# div_Ele.net
KiCad netlist of a schematic drawn in Altium Designer
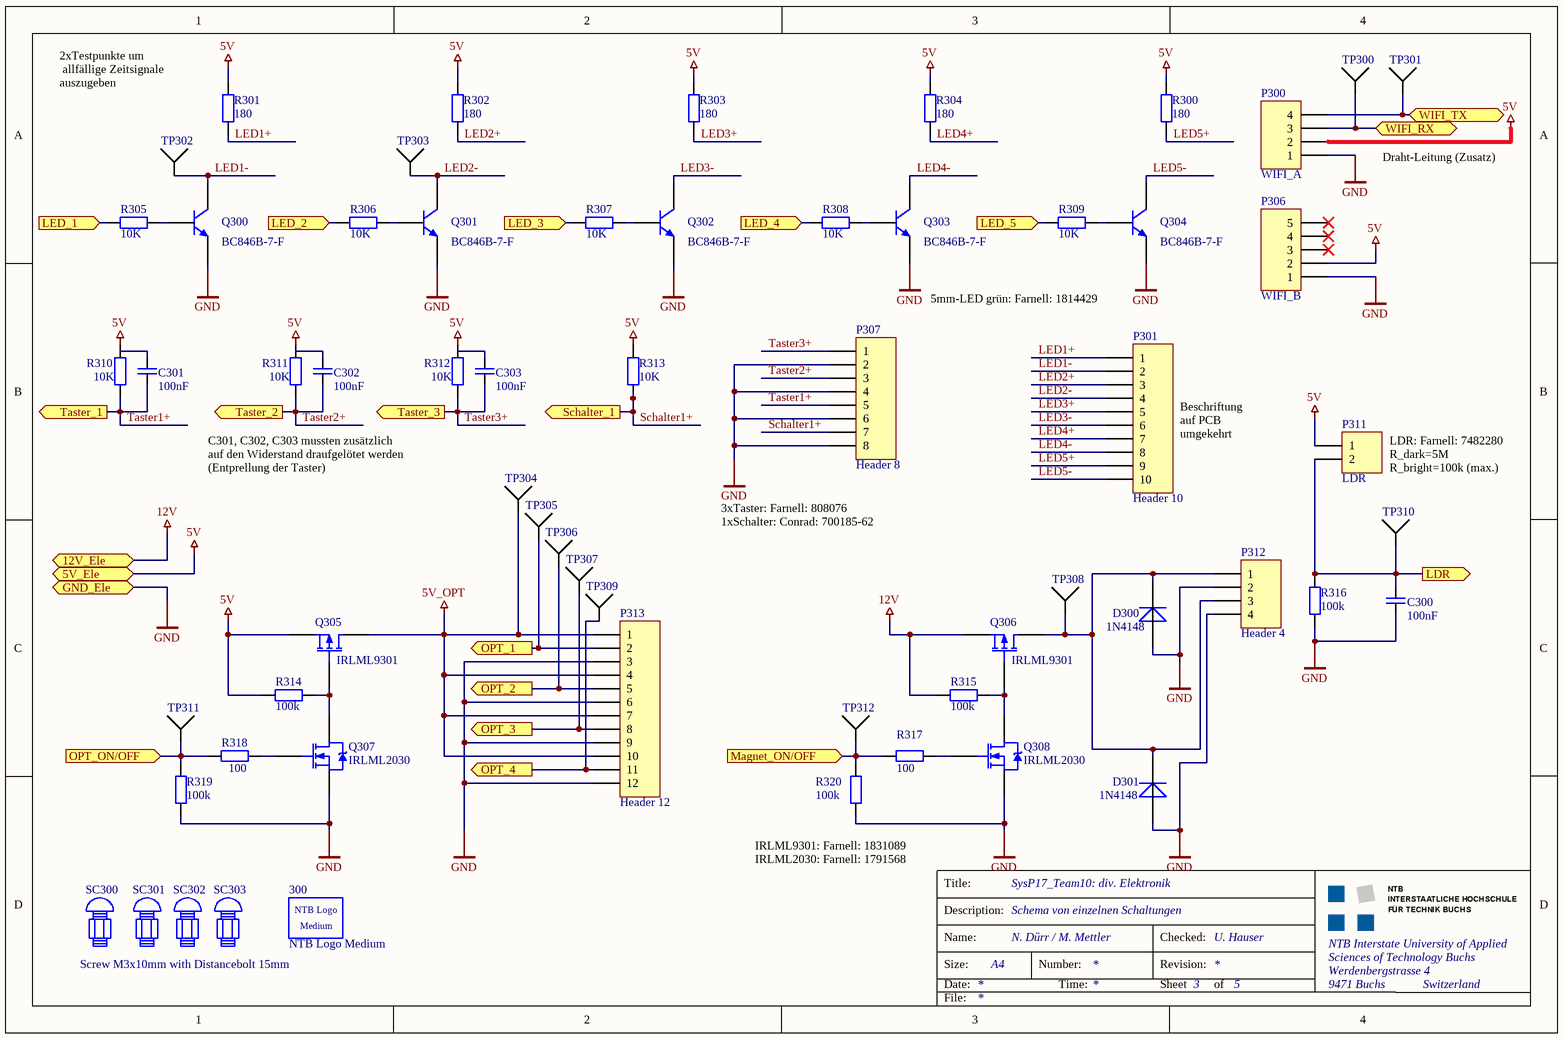
[diagram p0: div_Ele.SchDoc]

(export (version "E")
  (design (tool "Eeschema 10.0.6"))
  (components
    (comp (ref "300")
      (value "NTB Logo Medium")
      (footprint "NTB Logo Medium")
      (libsource (lib "IR-Sensor") (part "NTB Logo Medium"))
    )
    (comp (ref "C300")
      (value "100nF")
      (footprint "CAPC0805")
      (description "X7R MLCC 0805 (2012 Metric)")
      (fields (field (name "TOLERANCE") "10%"))
      (libsource (lib "Motortreiber") (part "C Bipolar 0805"))
    )
    (comp (ref "C301")
      (value "100nF")
      (footprint "CAPC0805")
      (description "X7R MLCC 0805 (2012 Metric)")
      (fields (field (name "TOLERANCE") "10%"))
      (libsource (lib "Motortreiber") (part "C Bipolar 0805"))
    )
    (comp (ref "C302")
      (value "100nF")
      (footprint "CAPC0805")
      (description "X7R MLCC 0805 (2012 Metric)")
      (fields (field (name "TOLERANCE") "10%"))
      (libsource (lib "Motortreiber") (part "C Bipolar 0805"))
    )
    (comp (ref "C303")
      (value "100nF")
      (footprint "CAPC0805")
      (description "X7R MLCC 0805 (2012 Metric)")
      (fields (field (name "TOLERANCE") "10%"))
      (libsource (lib "Motortreiber") (part "C Bipolar 0805"))
    )
    (comp (ref "D300")
      (value "1N4148")
      (footprint "SMD_2Pin_Diode")
      (description "High Conductance Fast Diode")
      (fields (field (name "#PUBLISHER") "Dr. A. Heinzelmann"))
      (libsource (lib "SysP2011") (part "1N4148"))
    )
    (comp (ref "D301")
      (value "1N4148")
      (footprint "SMD_2Pin_Diode")
      (description "High Conductance Fast Diode")
      (fields (field (name "#PUBLISHER") "Dr. A. Heinzelmann"))
      (libsource (lib "SysP2011") (part "1N4148"))
    )
    (comp (ref "P300")
      (value "WIFI_A")
      (footprint "HDR1X4")
      (description "Header, 4-Pin")
      (fields (field (name "PUBLISHER") "Altium Limited"))
      (libsource (lib "Miscellaneous Connectors") (part "Header 4"))
    )
    (comp (ref "P301")
      (value "Header 10")
      (footprint "HDR1X10")
      (description "Header, 10-Pin")
      (fields (field (name "PUBLISHER") "Altium Limited"))
      (libsource (lib "Miscellaneous Connectors") (part "Header 10"))
    )
    (comp (ref "P306")
      (value "WIFI_B")
      (footprint "HDR1X5")
      (description "Header, 5-Pin")
      (fields (field (name "PUBLISHER") "Altium Limited"))
      (libsource (lib "Miscellaneous Connectors") (part "Header 5"))
    )
    (comp (ref "P307")
      (value "Header 8")
      (footprint "HDR1X8")
      (description "Header, 8-Pin")
      (fields (field (name "PUBLISHER") "Altium Limited"))
      (libsource (lib "Miscellaneous Connectors") (part "Header 8"))
    )
    (comp (ref "P311")
      (value "LDR")
      (footprint "2Pin Header 2.54mm")
      (description "Header, 2-Pin")
      (fields (field (name "PUBLISHER") "Altium Limited"))
      (libsource (lib "Miscellaneous Connectors") (part "Header 2"))
    )
    (comp (ref "P312")
      (value "Header 4")
      (footprint "HDR1X4")
      (description "Header, 4-Pin")
      (fields (field (name "PUBLISHER") "Altium Limited"))
      (libsource (lib "") (part "Header 4_1"))
    )
    (comp (ref "P313")
      (value "Header 12")
      (footprint "HDR1X12")
      (description "Header, 12-Pin")
      (fields (field (name "PUBLISHER") "Altium Limited"))
      (libsource (lib "Miscellaneous Connectors") (part "Header 12"))
    )
    (comp (ref "Q300")
      (value "BC846B-7-F")
      (footprint "DIODS_SOT23_1B2E3C_3_H")
      (description "NPN General-purpose Transistor")
      (fields (field (name "MANUFACTURER") "DIODES INC") (field (name "PUBLISHER") "Altium Limited"))
      (libsource (lib "IR-Sensor_update") (part "DIODS_BC846B-7-F_SOT23"))
    )
    (comp (ref "Q301")
      (value "BC846B-7-F")
      (footprint "DIODS_SOT23_1B2E3C_3_H")
      (description "NPN General-purpose Transistor")
      (fields (field (name "MANUFACTURER") "DIODES INC") (field (name "PUBLISHER") "Altium Limited"))
      (libsource (lib "IR-Sensor_update") (part "DIODS_BC846B-7-F_SOT23"))
    )
    (comp (ref "Q302")
      (value "BC846B-7-F")
      (footprint "DIODS_SOT23_1B2E3C_3_H")
      (description "NPN General-purpose Transistor")
      (fields (field (name "MANUFACTURER") "DIODES INC") (field (name "PUBLISHER") "Altium Limited"))
      (libsource (lib "IR-Sensor_update") (part "DIODS_BC846B-7-F_SOT23"))
    )
    (comp (ref "Q303")
      (value "BC846B-7-F")
      (footprint "DIODS_SOT23_1B2E3C_3_H")
      (description "NPN General-purpose Transistor")
      (fields (field (name "MANUFACTURER") "DIODES INC") (field (name "PUBLISHER") "Altium Limited"))
      (libsource (lib "IR-Sensor_update") (part "DIODS_BC846B-7-F_SOT23"))
    )
    (comp (ref "Q304")
      (value "BC846B-7-F")
      (footprint "DIODS_SOT23_1B2E3C_3_H")
      (description "NPN General-purpose Transistor")
      (fields (field (name "MANUFACTURER") "DIODES INC") (field (name "PUBLISHER") "Altium Limited"))
      (libsource (lib "IR-Sensor_update") (part "DIODS_BC846B-7-F_SOT23"))
    )
    (comp (ref "Q305")
      (value "IRLML9301")
      (footprint "SOT23_L")
      (description "P-Channel MOSFET")
      (fields (field (name "PUBLISHER") "Altium Limited"))
      (libsource (lib "Miscellaneous Devices") (part "MOSFET-P"))
    )
    (comp (ref "Q306")
      (value "IRLML9301")
      (footprint "SOT23_L")
      (description "P-Channel MOSFET")
      (fields (field (name "PUBLISHER") "Altium Limited"))
      (libsource (lib "Miscellaneous Devices") (part "MOSFET-P"))
    )
    (comp (ref "Q307")
      (value "IRLML2030")
      (footprint "SOT23_L")
      (description "N-Channel Power MOSFET")
      (fields (field (name "PUBLISHER") "Altium Limited"))
      (libsource (lib "Miscellaneous Devices") (part "NMOS-2"))
    )
    (comp (ref "Q308")
      (value "IRLML2030")
      (footprint "SOT23_L")
      (description "N-Channel Power MOSFET")
      (fields (field (name "PUBLISHER") "Altium Limited"))
      (libsource (lib "Miscellaneous Devices") (part "NMOS-2"))
    )
    (comp (ref "R300")
      (value "180")
      (footprint "GEN_R0805_H")
      (description "generic resistor")
      (fields
        (field (name "MANUFACTURER") "Tbd")
        (field (name "Comment") "Generic")
        (field (name "PUBLISHER") "Altium Limited")
      )
      (libsource (lib "") (part "GEN_R_2_1"))
    )
    (comp (ref "R301")
      (value "180")
      (footprint "GEN_R0805_H")
      (description "generic resistor")
      (fields
        (field (name "MANUFACTURER") "Tbd")
        (field (name "Comment") "Generic")
        (field (name "PUBLISHER") "Altium Limited")
      )
      (libsource (lib "") (part "GEN_R_2_1"))
    )
    (comp (ref "R302")
      (value "180")
      (footprint "GEN_R0805_H")
      (description "generic resistor")
      (fields
        (field (name "MANUFACTURER") "Tbd")
        (field (name "Comment") "Generic")
        (field (name "PUBLISHER") "Altium Limited")
      )
      (libsource (lib "") (part "GEN_R_2_1"))
    )
    (comp (ref "R303")
      (value "180")
      (footprint "GEN_R0805_H")
      (description "generic resistor")
      (fields
        (field (name "MANUFACTURER") "Tbd")
        (field (name "Comment") "Generic")
        (field (name "PUBLISHER") "Altium Limited")
      )
      (libsource (lib "") (part "GEN_R_2_1"))
    )
    (comp (ref "R304")
      (value "180")
      (footprint "GEN_R0805_H")
      (description "generic resistor")
      (fields
        (field (name "MANUFACTURER") "Tbd")
        (field (name "Comment") "Generic")
        (field (name "PUBLISHER") "Altium Limited")
      )
      (libsource (lib "") (part "GEN_R_2_1"))
    )
    (comp (ref "R305")
      (value "10K")
      (footprint "GEN_R0805_H")
      (description "generic resistor")
      (fields
        (field (name "MANUFACTURER") "Tbd")
        (field (name "Comment") "Generic")
        (field (name "PUBLISHER") "Altium Limited")
      )
      (libsource (lib "Motortreiber") (part "GEN_R_2"))
    )
    (comp (ref "R306")
      (value "10K")
      (footprint "GEN_R0805_H")
      (description "generic resistor")
      (fields
        (field (name "MANUFACTURER") "Tbd")
        (field (name "Comment") "Generic")
        (field (name "PUBLISHER") "Altium Limited")
      )
      (libsource (lib "Motortreiber") (part "GEN_R_2"))
    )
    (comp (ref "R307")
      (value "10K")
      (footprint "GEN_R0805_H")
      (description "generic resistor")
      (fields
        (field (name "MANUFACTURER") "Tbd")
        (field (name "Comment") "Generic")
        (field (name "PUBLISHER") "Altium Limited")
      )
      (libsource (lib "Motortreiber") (part "GEN_R_2"))
    )
    (comp (ref "R308")
      (value "10K")
      (footprint "GEN_R0805_H")
      (description "generic resistor")
      (fields
        (field (name "MANUFACTURER") "Tbd")
        (field (name "Comment") "Generic")
        (field (name "PUBLISHER") "Altium Limited")
      )
      (libsource (lib "Motortreiber") (part "GEN_R_2"))
    )
    (comp (ref "R309")
      (value "10K")
      (footprint "GEN_R0805_H")
      (description "generic resistor")
      (fields
        (field (name "MANUFACTURER") "Tbd")
        (field (name "Comment") "Generic")
        (field (name "PUBLISHER") "Altium Limited")
      )
      (libsource (lib "Motortreiber") (part "GEN_R_2"))
    )
    (comp (ref "R310")
      (value "10K")
      (footprint "GEN_R0805_H")
      (description "generic resistor")
      (fields
        (field (name "MANUFACTURER") "Tbd")
        (field (name "Comment") "Generic")
        (field (name "PUBLISHER") "Altium Limited")
      )
      (libsource (lib "") (part "GEN_R_2_1"))
    )
    (comp (ref "R311")
      (value "10K")
      (footprint "GEN_R0805_H")
      (description "generic resistor")
      (fields
        (field (name "MANUFACTURER") "Tbd")
        (field (name "Comment") "Generic")
        (field (name "PUBLISHER") "Altium Limited")
      )
      (libsource (lib "") (part "GEN_R_2_1"))
    )
    (comp (ref "R312")
      (value "10K")
      (footprint "GEN_R0805_H")
      (description "generic resistor")
      (fields
        (field (name "MANUFACTURER") "Tbd")
        (field (name "Comment") "Generic")
        (field (name "PUBLISHER") "Altium Limited")
      )
      (libsource (lib "") (part "GEN_R_2_1"))
    )
    (comp (ref "R313")
      (value "10K")
      (footprint "GEN_R0805_H")
      (description "generic resistor")
      (fields
        (field (name "MANUFACTURER") "Tbd")
        (field (name "Comment") "Generic")
        (field (name "PUBLISHER") "Altium Limited")
      )
      (libsource (lib "") (part "GEN_R_2_1"))
    )
    (comp (ref "R314")
      (value "100k")
      (footprint "GEN_R0805_H")
      (description "generic resistor")
      (fields
        (field (name "MANUFACTURER") "Tbd")
        (field (name "Comment") "Generic")
        (field (name "PUBLISHER") "Altium Limited")
      )
      (libsource (lib "") (part "GEN_R_2_2"))
    )
    (comp (ref "R315")
      (value "100k")
      (footprint "GEN_R0805_H")
      (description "generic resistor")
      (fields
        (field (name "MANUFACTURER") "Tbd")
        (field (name "Comment") "Generic")
        (field (name "PUBLISHER") "Altium Limited")
      )
      (libsource (lib "") (part "GEN_R_2_2"))
    )
    (comp (ref "R316")
      (value "100k")
      (footprint "GEN_R0805_H")
      (description "generic resistor")
      (fields
        (field (name "MANUFACTURER") "Tbd")
        (field (name "Comment") "Generic")
        (field (name "PUBLISHER") "Altium Limited")
      )
      (libsource (lib "") (part "GEN_R_2_1"))
    )
    (comp (ref "R317")
      (value "100")
      (footprint "GEN_R0805_H")
      (description "generic resistor")
      (fields
        (field (name "MANUFACTURER") "Tbd")
        (field (name "Comment") "Generic")
        (field (name "PUBLISHER") "Altium Limited")
      )
      (libsource (lib "") (part "GEN_R_2_2"))
    )
    (comp (ref "R318")
      (value "100")
      (footprint "GEN_R0805_H")
      (description "generic resistor")
      (fields
        (field (name "MANUFACTURER") "Tbd")
        (field (name "Comment") "Generic")
        (field (name "PUBLISHER") "Altium Limited")
      )
      (libsource (lib "") (part "GEN_R_2_2"))
    )
    (comp (ref "R319")
      (value "100k")
      (footprint "GEN_R0805_H")
      (description "generic resistor")
      (fields
        (field (name "MANUFACTURER") "Tbd")
        (field (name "Comment") "Generic")
        (field (name "PUBLISHER") "Altium Limited")
      )
      (libsource (lib "") (part "GEN_R_2_3"))
    )
    (comp (ref "R320")
      (value "100k")
      (footprint "GEN_R0805_H")
      (description "generic resistor")
      (fields
        (field (name "MANUFACTURER") "Tbd")
        (field (name "Comment") "Generic")
        (field (name "PUBLISHER") "Altium Limited")
      )
      (libsource (lib "") (part "GEN_R_2_3"))
    )
    (comp (ref "SC300")
      (value "Screw M3x10mm with Distancebolt 15mm")
      (footprint "Screw_M3x10_Dist_15mm")
      (libsource (lib "Screw M3x10mm with Distancebolt 15mm") (part "Screw M3 10mm with Distancebolt 15mm"))
    )
    (comp (ref "SC301")
      (value "Screw M3x10mm with Distancebolt 15mm")
      (footprint "Screw_M3x10_Dist_15mm")
      (libsource (lib "Screw M3x10mm with Distancebolt 15mm") (part "Screw M3 10mm with Distancebolt 15mm"))
    )
    (comp (ref "SC302")
      (value "Screw M3x10mm with Distancebolt 15mm")
      (footprint "Screw_M3x10_Dist_15mm")
      (libsource (lib "Screw M3x10mm with Distancebolt 15mm") (part "Screw M3 10mm with Distancebolt 15mm"))
    )
    (comp (ref "SC303")
      (value "Screw M3x10mm with Distancebolt 15mm")
      (footprint "Screw_M3x10_Dist_15mm")
      (libsource (lib "Screw M3x10mm with Distancebolt 15mm") (part "Screw M3 10mm with Distancebolt 15mm"))
    )
    (comp (ref "TP300")
      (value "Testpunkt 1mm")
      (footprint "GEN_TP-THT-1.1mm_1_H")
      (fields (field (name "MANUFACTURER") "Keystone Electronics") (field (name "PUBLISHER") "B.Sc. Ursella"))
      (libsource (lib "IR-Sensor") (part "Testpunkt 1mm"))
    )
    (comp (ref "TP301")
      (value "Testpunkt 1mm")
      (footprint "GEN_TP-THT-1.1mm_1_H")
      (fields (field (name "MANUFACTURER") "Keystone Electronics") (field (name "PUBLISHER") "B.Sc. Ursella"))
      (libsource (lib "IR-Sensor") (part "Testpunkt 1mm"))
    )
    (comp (ref "TP302")
      (value "Testpunkt 1mm")
      (footprint "GEN_TP-THT-1.1mm_1_H")
      (fields (field (name "MANUFACTURER") "Keystone Electronics") (field (name "PUBLISHER") "B.Sc. Ursella"))
      (libsource (lib "IR-Sensor") (part "Testpunkt 1mm"))
    )
    (comp (ref "TP303")
      (value "Testpunkt 1mm")
      (footprint "GEN_TP-THT-1.1mm_1_H")
      (fields (field (name "MANUFACTURER") "Keystone Electronics") (field (name "PUBLISHER") "B.Sc. Ursella"))
      (libsource (lib "IR-Sensor") (part "Testpunkt 1mm"))
    )
    (comp (ref "TP304")
      (value "Testpunkt 1mm")
      (footprint "GEN_TP-THT-1.1mm_1_H")
      (fields (field (name "MANUFACTURER") "Keystone Electronics") (field (name "PUBLISHER") "B.Sc. Ursella"))
      (libsource (lib "IR-Sensor") (part "Testpunkt 1mm"))
    )
    (comp (ref "TP305")
      (value "Testpunkt 1mm")
      (footprint "GEN_TP-THT-1.1mm_1_H")
      (fields (field (name "MANUFACTURER") "Keystone Electronics") (field (name "PUBLISHER") "B.Sc. Ursella"))
      (libsource (lib "IR-Sensor") (part "Testpunkt 1mm"))
    )
    (comp (ref "TP306")
      (value "Testpunkt 1mm")
      (footprint "GEN_TP-THT-1.1mm_1_H")
      (fields (field (name "MANUFACTURER") "Keystone Electronics") (field (name "PUBLISHER") "B.Sc. Ursella"))
      (libsource (lib "IR-Sensor") (part "Testpunkt 1mm"))
    )
    (comp (ref "TP307")
      (value "Testpunkt 1mm")
      (footprint "GEN_TP-THT-1.1mm_1_H")
      (fields (field (name "MANUFACTURER") "Keystone Electronics") (field (name "PUBLISHER") "B.Sc. Ursella"))
      (libsource (lib "IR-Sensor") (part "Testpunkt 1mm"))
    )
    (comp (ref "TP308")
      (value "Testpunkt 1mm")
      (footprint "GEN_TP-THT-1.1mm_1_H")
      (fields (field (name "MANUFACTURER") "Keystone Electronics") (field (name "PUBLISHER") "B.Sc. Ursella"))
      (libsource (lib "IR-Sensor") (part "Testpunkt 1mm"))
    )
    (comp (ref "TP309")
      (value "Testpunkt 1mm")
      (footprint "GEN_TP-THT-1.1mm_1_H")
      (fields (field (name "MANUFACTURER") "Keystone Electronics") (field (name "PUBLISHER") "B.Sc. Ursella"))
      (libsource (lib "IR-Sensor") (part "Testpunkt 1mm"))
    )
    (comp (ref "TP310")
      (value "Testpunkt 1mm")
      (footprint "GEN_TP-THT-1.1mm_1_H")
      (fields (field (name "MANUFACTURER") "Keystone Electronics") (field (name "PUBLISHER") "B.Sc. Ursella"))
      (libsource (lib "IR-Sensor") (part "Testpunkt 1mm"))
    )
    (comp (ref "TP311")
      (value "Testpunkt 1mm")
      (footprint "GEN_TP-THT-1.1mm_1_H")
      (fields (field (name "MANUFACTURER") "Keystone Electronics") (field (name "PUBLISHER") "B.Sc. Ursella"))
      (libsource (lib "IR-Sensor") (part "Testpunkt 1mm"))
    )
    (comp (ref "TP312")
      (value "Testpunkt 1mm")
      (footprint "GEN_TP-THT-1.1mm_1_H")
      (fields (field (name "MANUFACTURER") "Keystone Electronics") (field (name "PUBLISHER") "B.Sc. Ursella"))
      (libsource (lib "IR-Sensor") (part "Testpunkt 1mm"))
    )
  )
  (nets
    (net (code "1") (name "/LDR") (class "Default")
      (node (ref "C300") (pin "1") (pinfunction "1_1") (pintype "passive"))
      (node (ref "P311") (pin "2") (pinfunction "2_2") (pintype "passive"))
      (node (ref "R316") (pin "1") (pinfunction "1_1") (pintype "passive"))
      (node (ref "TP310") (pin "1") (pinfunction "0_1") (pintype "passive"))
    )
    (net (code "2") (name "/LED1+") (class "Default")
      (node (ref "P301") (pin "1") (pinfunction "1_1") (pintype "passive"))
      (node (ref "R301") (pin "2") (pinfunction "2_2") (pintype "passive"))
    )
    (net (code "3") (name "/LED1-") (class "Default")
      (node (ref "P301") (pin "2") (pinfunction "2_2") (pintype "passive"))
      (node (ref "Q300") (pin "3") (pinfunction "C_3") (pintype "passive"))
      (node (ref "TP302") (pin "1") (pinfunction "0_1") (pintype "passive"))
    )
    (net (code "4") (name "/LED2+") (class "Default")
      (node (ref "P301") (pin "3") (pinfunction "3_3") (pintype "passive"))
      (node (ref "R302") (pin "2") (pinfunction "2_2") (pintype "passive"))
    )
    (net (code "5") (name "/LED2-") (class "Default")
      (node (ref "P301") (pin "4") (pinfunction "4_4") (pintype "passive"))
      (node (ref "Q301") (pin "3") (pinfunction "C_3") (pintype "passive"))
      (node (ref "TP303") (pin "1") (pinfunction "0_1") (pintype "passive"))
    )
    (net (code "6") (name "/LED3+") (class "Default")
      (node (ref "P301") (pin "5") (pinfunction "5_5") (pintype "passive"))
      (node (ref "R303") (pin "2") (pinfunction "2_2") (pintype "passive"))
    )
    (net (code "7") (name "/LED3-") (class "Default")
      (node (ref "P301") (pin "6") (pinfunction "6_6") (pintype "passive"))
      (node (ref "Q302") (pin "3") (pinfunction "C_3") (pintype "passive"))
    )
    (net (code "8") (name "/LED4+") (class "Default")
      (node (ref "P301") (pin "7") (pinfunction "7_7") (pintype "passive"))
      (node (ref "R304") (pin "2") (pinfunction "2_2") (pintype "passive"))
    )
    (net (code "9") (name "/LED4-") (class "Default")
      (node (ref "P301") (pin "8") (pinfunction "8_8") (pintype "passive"))
      (node (ref "Q303") (pin "3") (pinfunction "C_3") (pintype "passive"))
    )
    (net (code "10") (name "/LED5+") (class "Default")
      (node (ref "P301") (pin "9") (pinfunction "9_9") (pintype "passive"))
      (node (ref "R300") (pin "2") (pinfunction "2_2") (pintype "passive"))
    )
    (net (code "11") (name "/LED5-") (class "Default")
      (node (ref "P301") (pin "10") (pinfunction "10_10") (pintype "passive"))
      (node (ref "Q304") (pin "3") (pinfunction "C_3") (pintype "passive"))
    )
    (net (code "12") (name "/LED_1") (class "Default")
      (node (ref "R305") (pin "1") (pinfunction "1_1") (pintype "passive"))
    )
    (net (code "13") (name "/LED_2") (class "Default")
      (node (ref "R306") (pin "1") (pinfunction "1_1") (pintype "passive"))
    )
    (net (code "14") (name "/LED_3") (class "Default")
      (node (ref "R307") (pin "1") (pinfunction "1_1") (pintype "passive"))
    )
    (net (code "15") (name "/LED_4") (class "Default")
      (node (ref "R308") (pin "1") (pinfunction "1_1") (pintype "passive"))
    )
    (net (code "16") (name "/LED_5") (class "Default")
      (node (ref "R309") (pin "1") (pinfunction "1_1") (pintype "passive"))
    )
    (net (code "17") (name "/Magnet_ON{slash}OFF") (class "Default")
      (node (ref "R317") (pin "2") (pinfunction "2_2") (pintype "passive"))
      (node (ref "R320") (pin "2") (pinfunction "2_2") (pintype "passive"))
      (node (ref "TP312") (pin "1") (pinfunction "0_1") (pintype "passive"))
    )
    (net (code "18") (name "/OPT_1") (class "Default")
      (node (ref "P313") (pin "2") (pinfunction "2_2") (pintype "passive"))
      (node (ref "TP305") (pin "1") (pinfunction "0_1") (pintype "passive"))
    )
    (net (code "19") (name "/OPT_2") (class "Default")
      (node (ref "P313") (pin "5") (pinfunction "5_5") (pintype "passive"))
      (node (ref "TP306") (pin "1") (pinfunction "0_1") (pintype "passive"))
    )
    (net (code "20") (name "/OPT_3") (class "Default")
      (node (ref "P313") (pin "8") (pinfunction "8_8") (pintype "passive"))
      (node (ref "TP307") (pin "1") (pinfunction "0_1") (pintype "passive"))
    )
    (net (code "21") (name "/OPT_4") (class "Default")
      (node (ref "P313") (pin "11") (pinfunction "11_11") (pintype "passive"))
      (node (ref "TP309") (pin "1") (pinfunction "0_1") (pintype "passive"))
    )
    (net (code "22") (name "/OPT_ON{slash}OFF") (class "Default")
      (node (ref "R318") (pin "2") (pinfunction "2_2") (pintype "passive"))
      (node (ref "R319") (pin "2") (pinfunction "2_2") (pintype "passive"))
      (node (ref "TP311") (pin "1") (pinfunction "0_1") (pintype "passive"))
    )
    (net (code "23") (name "/Schalter1+") (class "Default")
      (node (ref "P307") (pin "7") (pinfunction "7_7") (pintype "passive"))
      (node (ref "R313") (pin "2") (pinfunction "2_2") (pintype "passive"))
    )
    (net (code "24") (name "/Taster1+") (class "Default")
      (node (ref "C301") (pin "2") (pinfunction "2_2") (pintype "passive"))
      (node (ref "P307") (pin "5") (pinfunction "5_5") (pintype "passive"))
      (node (ref "R310") (pin "2") (pinfunction "2_2") (pintype "passive"))
    )
    (net (code "25") (name "/Taster2+") (class "Default")
      (node (ref "C302") (pin "2") (pinfunction "2_2") (pintype "passive"))
      (node (ref "P307") (pin "3") (pinfunction "3_3") (pintype "passive"))
      (node (ref "R311") (pin "2") (pinfunction "2_2") (pintype "passive"))
    )
    (net (code "26") (name "/Taster3+") (class "Default")
      (node (ref "C303") (pin "2") (pinfunction "2_2") (pintype "passive"))
      (node (ref "P307") (pin "1") (pinfunction "1_1") (pintype "passive"))
      (node (ref "R312") (pin "2") (pinfunction "2_2") (pintype "passive"))
    )
    (net (code "27") (name "/WIFI_RX") (class "Default")
      (node (ref "P300") (pin "3") (pinfunction "3_3") (pintype "passive"))
      (node (ref "TP300") (pin "1") (pinfunction "0_1") (pintype "passive"))
    )
    (net (code "28") (name "/WIFI_TX") (class "Default")
      (node (ref "P300") (pin "4") (pinfunction "4_4") (pintype "passive"))
      (node (ref "TP301") (pin "1") (pinfunction "0_1") (pintype "passive"))
    )
    (net (code "29") (name "5V") (class "Default")
      (node (ref "P300") (pin "2") (pinfunction "2_2") (pintype "passive"))
      (node (ref "P306") (pin "2") (pinfunction "2_2") (pintype "passive"))
      (node (ref "P311") (pin "1") (pinfunction "1_1") (pintype "passive"))
      (node (ref "Q305") (pin "2") (pinfunction "S_2") (pintype "passive"))
      (node (ref "R300") (pin "1") (pinfunction "1_1") (pintype "passive"))
      (node (ref "R301") (pin "1") (pinfunction "1_1") (pintype "passive"))
      (node (ref "R302") (pin "1") (pinfunction "1_1") (pintype "passive"))
      (node (ref "R303") (pin "1") (pinfunction "1_1") (pintype "passive"))
      (node (ref "R304") (pin "1") (pinfunction "1_1") (pintype "passive"))
      (node (ref "R310") (pin "1") (pinfunction "1_1") (pintype "passive"))
      (node (ref "R311") (pin "1") (pinfunction "1_1") (pintype "passive"))
      (node (ref "R312") (pin "1") (pinfunction "1_1") (pintype "passive"))
      (node (ref "R313") (pin "1") (pinfunction "1_1") (pintype "passive"))
      (node (ref "R314") (pin "2") (pinfunction "2_2") (pintype "passive"))
    )
    (net (code "30") (name "5V_OPT") (class "Default")
      (node (ref "P313") (pin "1") (pinfunction "1_1") (pintype "passive"))
      (node (ref "P313") (pin "10") (pinfunction "10_10") (pintype "passive"))
      (node (ref "P313") (pin "4") (pinfunction "4_4") (pintype "passive"))
      (node (ref "P313") (pin "7") (pinfunction "7_7") (pintype "passive"))
      (node (ref "Q305") (pin "1") (pinfunction "D_1") (pintype "passive"))
      (node (ref "TP304") (pin "1") (pinfunction "0_1") (pintype "passive"))
    )
    (net (code "31") (name "12V") (class "Default")
      (node (ref "Q306") (pin "2") (pinfunction "S_2") (pintype "passive"))
      (node (ref "R315") (pin "2") (pinfunction "2_2") (pintype "passive"))
    )
    (net (code "32") (name "GND") (class "Default")
      (node (ref "C300") (pin "2") (pinfunction "2_2") (pintype "passive"))
      (node (ref "D300") (pin "2") (pinfunction "A_2") (pintype "passive"))
      (node (ref "D301") (pin "2") (pinfunction "A_2") (pintype "passive"))
      (node (ref "P300") (pin "1") (pinfunction "1_1") (pintype "passive"))
      (node (ref "P306") (pin "1") (pinfunction "1_1") (pintype "passive"))
      (node (ref "P307") (pin "2") (pinfunction "2_2") (pintype "passive"))
      (node (ref "P307") (pin "4") (pinfunction "4_4") (pintype "passive"))
      (node (ref "P307") (pin "6") (pinfunction "6_6") (pintype "passive"))
      (node (ref "P307") (pin "8") (pinfunction "8_8") (pintype "passive"))
      (node (ref "P312") (pin "2") (pinfunction "2_2") (pintype "passive"))
      (node (ref "P312") (pin "4") (pinfunction "4_4") (pintype "passive"))
      (node (ref "P313") (pin "12") (pinfunction "12_12") (pintype "passive"))
      (node (ref "P313") (pin "3") (pinfunction "3_3") (pintype "passive"))
      (node (ref "P313") (pin "6") (pinfunction "6_6") (pintype "passive"))
      (node (ref "P313") (pin "9") (pinfunction "9_9") (pintype "passive"))
      (node (ref "Q300") (pin "2") (pinfunction "E_2") (pintype "passive"))
      (node (ref "Q301") (pin "2") (pinfunction "E_2") (pintype "passive"))
      (node (ref "Q302") (pin "2") (pinfunction "E_2") (pintype "passive"))
      (node (ref "Q303") (pin "2") (pinfunction "E_2") (pintype "passive"))
      (node (ref "Q304") (pin "2") (pinfunction "E_2") (pintype "passive"))
      (node (ref "Q307") (pin "2") (pinfunction "S_2") (pintype "passive"))
      (node (ref "Q308") (pin "2") (pinfunction "S_2") (pintype "passive"))
      (node (ref "R316") (pin "2") (pinfunction "2_2") (pintype "passive"))
      (node (ref "R319") (pin "1") (pinfunction "1_1") (pintype "passive"))
      (node (ref "R320") (pin "1") (pinfunction "1_1") (pintype "passive"))
    )
    (net (code "33") (name "Net-(D300-K)") (class "Default")
      (node (ref "D300") (pin "1") (pinfunction "K_1") (pintype "passive"))
      (node (ref "D301") (pin "1") (pinfunction "K_1") (pintype "passive"))
      (node (ref "P312") (pin "1") (pinfunction "1_1") (pintype "passive"))
      (node (ref "P312") (pin "3") (pinfunction "3_3") (pintype "passive"))
      (node (ref "Q306") (pin "1") (pinfunction "D_1") (pintype "passive"))
      (node (ref "TP308") (pin "1") (pinfunction "0_1") (pintype "passive"))
    )
    (net (code "34") (name "Net-(Q300-B)") (class "Default")
      (node (ref "Q300") (pin "1") (pinfunction "B_1") (pintype "passive"))
      (node (ref "R305") (pin "2") (pinfunction "2_2") (pintype "passive"))
    )
    (net (code "35") (name "Net-(Q301-B)") (class "Default")
      (node (ref "Q301") (pin "1") (pinfunction "B_1") (pintype "passive"))
      (node (ref "R306") (pin "2") (pinfunction "2_2") (pintype "passive"))
    )
    (net (code "36") (name "Net-(Q302-B)") (class "Default")
      (node (ref "Q302") (pin "1") (pinfunction "B_1") (pintype "passive"))
      (node (ref "R307") (pin "2") (pinfunction "2_2") (pintype "passive"))
    )
    (net (code "37") (name "Net-(Q303-B)") (class "Default")
      (node (ref "Q303") (pin "1") (pinfunction "B_1") (pintype "passive"))
      (node (ref "R308") (pin "2") (pinfunction "2_2") (pintype "passive"))
    )
    (net (code "38") (name "Net-(Q304-B)") (class "Default")
      (node (ref "Q304") (pin "1") (pinfunction "B_1") (pintype "passive"))
      (node (ref "R309") (pin "2") (pinfunction "2_2") (pintype "passive"))
    )
    (net (code "39") (name "Net-(Q305-G)") (class "Default")
      (node (ref "Q305") (pin "3") (pinfunction "G_3") (pintype "passive"))
      (node (ref "Q307") (pin "1") (pinfunction "D_1") (pintype "passive"))
      (node (ref "R314") (pin "1") (pinfunction "1_1") (pintype "passive"))
    )
    (net (code "40") (name "Net-(Q306-G)") (class "Default")
      (node (ref "Q306") (pin "3") (pinfunction "G_3") (pintype "passive"))
      (node (ref "Q308") (pin "1") (pinfunction "D_1") (pintype "passive"))
      (node (ref "R315") (pin "1") (pinfunction "1_1") (pintype "passive"))
    )
    (net (code "41") (name "Net-(Q307-G)") (class "Default")
      (node (ref "Q307") (pin "3") (pinfunction "G_3") (pintype "passive"))
      (node (ref "R318") (pin "1") (pinfunction "1_1") (pintype "passive"))
    )
    (net (code "42") (name "Net-(Q308-G)") (class "Default")
      (node (ref "Q308") (pin "3") (pinfunction "G_3") (pintype "passive"))
      (node (ref "R317") (pin "1") (pinfunction "1_1") (pintype "passive"))
    )
    (net (code "43") (name "unconnected-(C301-Pad1)") (class "Default")
      (node (ref "C301") (pin "1") (pinfunction "1_1") (pintype "passive"))
    )
    (net (code "44") (name "unconnected-(C302-Pad1)") (class "Default")
      (node (ref "C302") (pin "1") (pinfunction "1_1") (pintype "passive"))
    )
    (net (code "45") (name "unconnected-(C303-Pad1)") (class "Default")
      (node (ref "C303") (pin "1") (pinfunction "1_1") (pintype "passive"))
    )
    (net (code "46") (name "unconnected-(P306-Pad3)") (class "Default")
      (node (ref "P306") (pin "3") (pinfunction "3_3") (pintype "passive+no_connect"))
    )
    (net (code "47") (name "unconnected-(P306-Pad4)") (class "Default")
      (node (ref "P306") (pin "4") (pinfunction "4_4") (pintype "passive+no_connect"))
    )
    (net (code "48") (name "unconnected-(P306-Pad5)") (class "Default")
      (node (ref "P306") (pin "5") (pinfunction "5_5") (pintype "passive+no_connect"))
    )
  )
)
